# breakout_BGM111.net
KiCad netlist of a schematic drawn in EAGLE
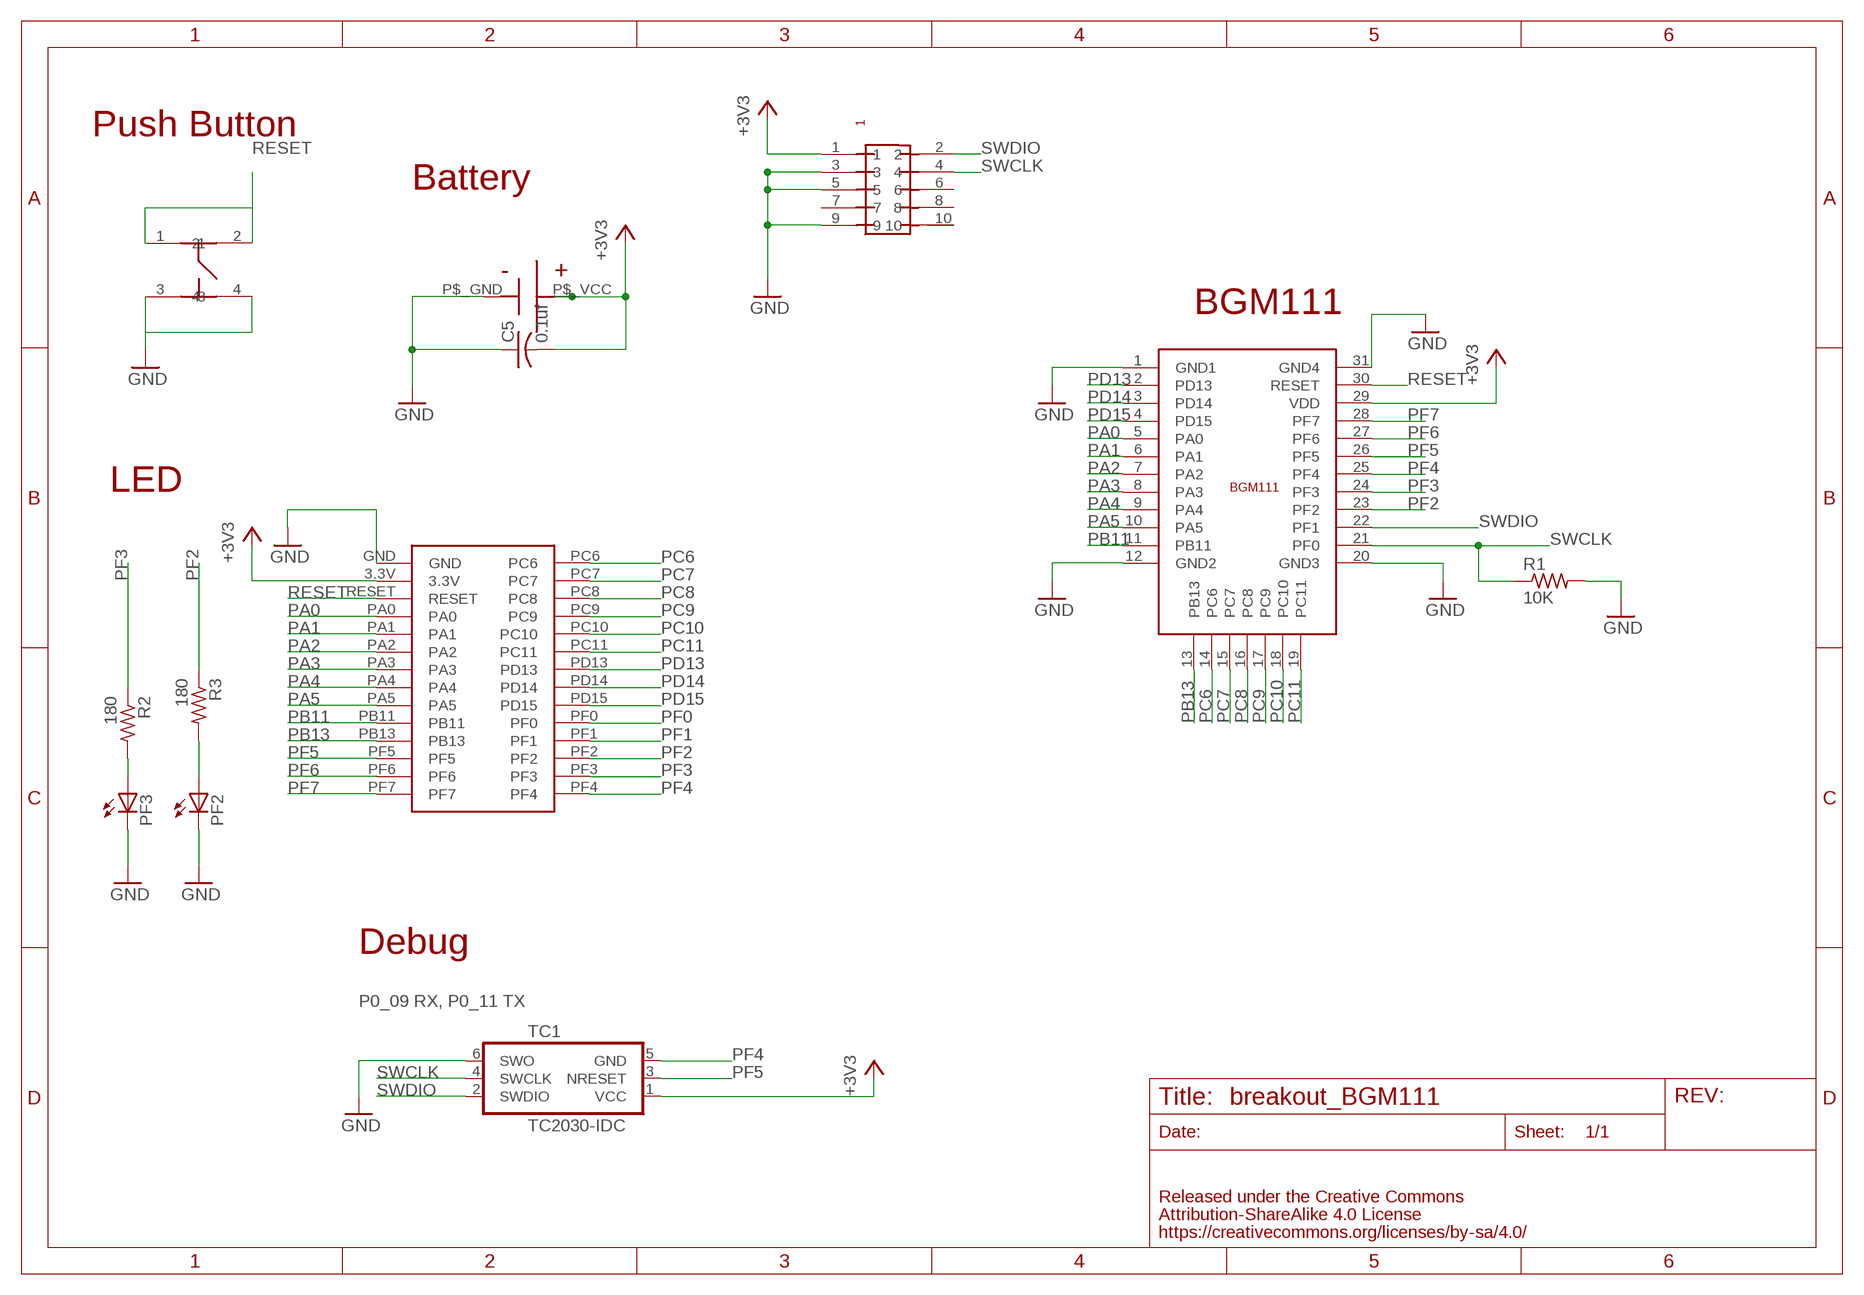
[diagram p0: schematic, sheet 1]

(export (version "E")
  (design (tool "Eeschema 10.0.6"))
  (components
    (comp (ref "C5")
      (value "0.1uf")
      (footprint "eagle-import:C0603")
      (libsource (lib "eagle-import") (part "C-USC0603"))
    )
    (comp (ref "PF2")
      (value "LEDCHIP-LED0603")
      (footprint "eagle-import:CHIP-LED0603")
      (libsource (lib "eagle-import") (part "LEDCHIP-LED0603"))
    )
    (comp (ref "PF3")
      (value "LEDCHIP-LED0603")
      (footprint "eagle-import:CHIP-LED0603")
      (libsource (lib "eagle-import") (part "LEDCHIP-LED0603"))
    )
    (comp (ref "R1")
      (value "10K")
      (footprint "eagle-import:R0603")
      (libsource (lib "eagle-import") (part "R-US_R0603"))
    )
    (comp (ref "R2")
      (value "180")
      (footprint "eagle-import:R0603")
      (libsource (lib "eagle-import") (part "R-US_R0603"))
    )
    (comp (ref "R3")
      (value "180")
      (footprint "eagle-import:R0603")
      (libsource (lib "eagle-import") (part "R-US_R0603"))
    )
    (comp (ref "TC1")
      (value "TC2030-IDC")
      (footprint "eagle-import:TC2030-IDC")
      (libsource (lib "eagle-import") (part "TC2030-IDC"))
    )
    (comp (ref "U$1")
      (value "SILICONLABS-BGM111")
      (footprint "eagle-import:SILICONLABS-BGM111")
      (libsource (lib "eagle-import") (part "SILICONLABS-BGM111"))
    )
    (comp (ref "U$2")
      (value "SMTU2450-TOP")
      (footprint "eagle-import:SMTU2450")
      (libsource (lib "eagle-import") (part "SMTU2450-TOP"))
    )
    (comp (ref "U$3")
      (value "BLE-BREAKOUT-NORDIC")
      (footprint "eagle-import:BLE-BREAKOUT-SILICONLABS")
      (libsource (lib "eagle-import") (part "BLE-BREAKOUT-NORDIC"))
    )
    (comp (ref "U$4")
      (value "PIN-HEADER-SMT(1.27MM)2X5")
      (footprint "eagle-import:PIN-HEADER-SMT(1.27MM)2X5")
      (libsource (lib "eagle-import") (part "PIN-HEADER-SMT(1.27MM)2X5"))
    )
    (comp (ref "U$5")
      (value "SWICTH-4P(KMR2)")
      (footprint "eagle-import:SWITCH-4P(KMR2)")
      (libsource (lib "eagle-import") (part "SWICTH-4P(KMR2)"))
    )
  )
  (nets
    (net (code "1") (name "+3V3") (class "Default")
      (node (ref "C5") (pin "2") (pinfunction "2_2") (pintype "passive"))
      (node (ref "TC1") (pin "1") (pinfunction "VCC_1") (pintype "passive"))
      (node (ref "U$1") (pin "29") (pinfunction "VDD_29") (pintype "bidirectional"))
      (node (ref "U$2") (pin "P$_VCC") (pinfunction "+_P$_VCC") (pintype "bidirectional"))
      (node (ref "U$3") (pin "3.3V") (pinfunction "3.3V_3.3V") (pintype "bidirectional"))
      (node (ref "U$4") (pin "1") (pinfunction "1_1") (pintype "bidirectional"))
    )
    (net (code "2") (name "/PA0") (class "Default")
      (node (ref "U$1") (pin "5") (pinfunction "PA0_5") (pintype "bidirectional"))
      (node (ref "U$3") (pin "PA0") (pinfunction "PA0_PA0") (pintype "bidirectional"))
    )
    (net (code "3") (name "/PA1") (class "Default")
      (node (ref "U$1") (pin "6") (pinfunction "PA1_6") (pintype "bidirectional"))
      (node (ref "U$3") (pin "PA1") (pinfunction "PA1_PA1") (pintype "bidirectional"))
    )
    (net (code "4") (name "/PA2") (class "Default")
      (node (ref "U$1") (pin "7") (pinfunction "PA2_7") (pintype "bidirectional"))
      (node (ref "U$3") (pin "PA2") (pinfunction "PA2_PA2") (pintype "bidirectional"))
    )
    (net (code "5") (name "/PA3") (class "Default")
      (node (ref "U$1") (pin "8") (pinfunction "PA3_8") (pintype "bidirectional"))
      (node (ref "U$3") (pin "PA3") (pinfunction "PA3_PA3") (pintype "bidirectional"))
    )
    (net (code "6") (name "/PA4") (class "Default")
      (node (ref "U$1") (pin "9") (pinfunction "PA4_9") (pintype "bidirectional"))
      (node (ref "U$3") (pin "PA4") (pinfunction "PA4_PA4") (pintype "bidirectional"))
    )
    (net (code "7") (name "/PA5") (class "Default")
      (node (ref "U$1") (pin "10") (pinfunction "PA5_10") (pintype "bidirectional"))
      (node (ref "U$3") (pin "PA5") (pinfunction "PA5_PA5") (pintype "bidirectional"))
    )
    (net (code "8") (name "/PB11") (class "Default")
      (node (ref "U$1") (pin "11") (pinfunction "PB11_11") (pintype "bidirectional"))
      (node (ref "U$3") (pin "PB11") (pinfunction "PB11_PB11") (pintype "bidirectional"))
    )
    (net (code "9") (name "/PB13") (class "Default")
      (node (ref "U$1") (pin "13") (pinfunction "PB13_13") (pintype "bidirectional"))
      (node (ref "U$3") (pin "PB13") (pinfunction "PB13_PB13") (pintype "bidirectional"))
    )
    (net (code "10") (name "/PC6") (class "Default")
      (node (ref "U$1") (pin "14") (pinfunction "PC6_14") (pintype "bidirectional"))
      (node (ref "U$3") (pin "PC6") (pinfunction "PC6_PC6") (pintype "bidirectional"))
    )
    (net (code "11") (name "/PC7") (class "Default")
      (node (ref "U$1") (pin "15") (pinfunction "PC7_15") (pintype "bidirectional"))
      (node (ref "U$3") (pin "PC7") (pinfunction "PC7_PC7") (pintype "bidirectional"))
    )
    (net (code "12") (name "/PC8") (class "Default")
      (node (ref "U$1") (pin "16") (pinfunction "PC8_16") (pintype "bidirectional"))
      (node (ref "U$3") (pin "PC8") (pinfunction "PC8_PC8") (pintype "bidirectional"))
    )
    (net (code "13") (name "/PC9") (class "Default")
      (node (ref "U$1") (pin "17") (pinfunction "PC9_17") (pintype "bidirectional"))
      (node (ref "U$3") (pin "PC9") (pinfunction "PC9_PC9") (pintype "bidirectional"))
    )
    (net (code "14") (name "/PC10") (class "Default")
      (node (ref "U$1") (pin "18") (pinfunction "PC10_18") (pintype "bidirectional"))
      (node (ref "U$3") (pin "PC10") (pinfunction "PC10_PC10") (pintype "bidirectional"))
    )
    (net (code "15") (name "/PC11") (class "Default")
      (node (ref "U$1") (pin "19") (pinfunction "PC11_19") (pintype "bidirectional"))
      (node (ref "U$3") (pin "PC11") (pinfunction "PC11_PC11") (pintype "bidirectional"))
    )
    (net (code "16") (name "/PD13") (class "Default")
      (node (ref "U$1") (pin "2") (pinfunction "PD13_2") (pintype "bidirectional"))
      (node (ref "U$3") (pin "PD13") (pinfunction "PD13_PD13") (pintype "bidirectional"))
    )
    (net (code "17") (name "/PD14") (class "Default")
      (node (ref "U$1") (pin "3") (pinfunction "PD14_3") (pintype "bidirectional"))
      (node (ref "U$3") (pin "PD14") (pinfunction "PD14_PD14") (pintype "bidirectional"))
    )
    (net (code "18") (name "/PD15") (class "Default")
      (node (ref "U$1") (pin "4") (pinfunction "PD15_4") (pintype "bidirectional"))
      (node (ref "U$3") (pin "PD15") (pinfunction "PD15_PD15") (pintype "bidirectional"))
    )
    (net (code "19") (name "/PF0") (class "Default")
      (node (ref "U$3") (pin "PF0") (pinfunction "PF0_PF0") (pintype "bidirectional"))
    )
    (net (code "20") (name "/PF1") (class "Default")
      (node (ref "U$3") (pin "PF1") (pinfunction "PF1_PF1") (pintype "bidirectional"))
    )
    (net (code "21") (name "/PF2") (class "Default")
      (node (ref "R3") (pin "1") (pinfunction "1_1") (pintype "passive"))
      (node (ref "U$1") (pin "23") (pinfunction "PF2_23") (pintype "bidirectional"))
      (node (ref "U$3") (pin "PF2") (pinfunction "PF2_PF2") (pintype "bidirectional"))
    )
    (net (code "22") (name "/PF3") (class "Default")
      (node (ref "R2") (pin "1") (pinfunction "1_1") (pintype "passive"))
      (node (ref "U$1") (pin "24") (pinfunction "PF3_24") (pintype "bidirectional"))
      (node (ref "U$3") (pin "PF3") (pinfunction "PF3_PF3") (pintype "bidirectional"))
    )
    (net (code "23") (name "/PF4") (class "Default")
      (node (ref "TC1") (pin "5") (pinfunction "GND_5") (pintype "passive"))
      (node (ref "U$1") (pin "25") (pinfunction "PF4_25") (pintype "bidirectional"))
      (node (ref "U$3") (pin "PF4") (pinfunction "PF4_PF4") (pintype "bidirectional"))
    )
    (net (code "24") (name "/PF5") (class "Default")
      (node (ref "TC1") (pin "3") (pinfunction "NRESET_3") (pintype "passive"))
      (node (ref "U$1") (pin "26") (pinfunction "PF5_26") (pintype "bidirectional"))
      (node (ref "U$3") (pin "PF5") (pinfunction "PF5_PF5") (pintype "bidirectional"))
    )
    (net (code "25") (name "/PF6") (class "Default")
      (node (ref "U$1") (pin "27") (pinfunction "PF6_27") (pintype "bidirectional"))
      (node (ref "U$3") (pin "PF6") (pinfunction "PF6_PF6") (pintype "bidirectional"))
    )
    (net (code "26") (name "/PF7") (class "Default")
      (node (ref "U$1") (pin "28") (pinfunction "PF7_28") (pintype "bidirectional"))
      (node (ref "U$3") (pin "PF7") (pinfunction "PF7_PF7") (pintype "bidirectional"))
    )
    (net (code "27") (name "/RESET") (class "Default")
      (node (ref "U$1") (pin "30") (pinfunction "RESET_30") (pintype "bidirectional"))
      (node (ref "U$3") (pin "RESET") (pinfunction "RESET_RESET") (pintype "bidirectional"))
      (node (ref "U$5") (pin "1") (pinfunction "1_1") (pintype "bidirectional"))
      (node (ref "U$5") (pin "2") (pinfunction "2_2") (pintype "bidirectional"))
    )
    (net (code "28") (name "/SWCLK") (class "Default")
      (node (ref "R1") (pin "1") (pinfunction "1_1") (pintype "passive"))
      (node (ref "TC1") (pin "4") (pinfunction "SWCLK_4") (pintype "passive"))
      (node (ref "U$1") (pin "21") (pinfunction "PF0_21") (pintype "bidirectional"))
      (node (ref "U$4") (pin "4") (pinfunction "4_4") (pintype "bidirectional"))
    )
    (net (code "29") (name "/SWDIO") (class "Default")
      (node (ref "TC1") (pin "2") (pinfunction "SWDIO_2") (pintype "passive"))
      (node (ref "U$1") (pin "22") (pinfunction "PF1_22") (pintype "bidirectional"))
      (node (ref "U$4") (pin "2") (pinfunction "2_2") (pintype "bidirectional"))
    )
    (net (code "30") (name "GND") (class "Default")
      (node (ref "C5") (pin "1") (pinfunction "1_1") (pintype "passive"))
      (node (ref "PF2") (pin "C") (pinfunction "C_C") (pintype "passive"))
      (node (ref "PF3") (pin "C") (pinfunction "C_C") (pintype "passive"))
      (node (ref "R1") (pin "2") (pinfunction "2_2") (pintype "passive"))
      (node (ref "TC1") (pin "6") (pinfunction "SWO_6") (pintype "passive"))
      (node (ref "U$1") (pin "1") (pinfunction "GND1_1") (pintype "bidirectional"))
      (node (ref "U$1") (pin "12") (pinfunction "GND2_12") (pintype "bidirectional"))
      (node (ref "U$1") (pin "20") (pinfunction "GND3_20") (pintype "bidirectional"))
      (node (ref "U$1") (pin "31") (pinfunction "GND4_31") (pintype "bidirectional"))
      (node (ref "U$2") (pin "P$_GND") (pinfunction "-_P$_GND") (pintype "bidirectional"))
      (node (ref "U$3") (pin "GND") (pinfunction "GND_GND") (pintype "bidirectional"))
      (node (ref "U$4") (pin "3") (pinfunction "3_3") (pintype "bidirectional"))
      (node (ref "U$4") (pin "5") (pinfunction "5_5") (pintype "bidirectional"))
      (node (ref "U$4") (pin "9") (pinfunction "9_9") (pintype "bidirectional"))
      (node (ref "U$5") (pin "3") (pinfunction "3_3") (pintype "bidirectional"))
      (node (ref "U$5") (pin "4") (pinfunction "4_4") (pintype "bidirectional"))
    )
    (net (code "31") (name "Net-(PF2-PadA)") (class "Default")
      (node (ref "PF2") (pin "A") (pinfunction "A_A") (pintype "passive"))
      (node (ref "R3") (pin "2") (pinfunction "2_2") (pintype "passive"))
    )
    (net (code "32") (name "Net-(PF3-PadA)") (class "Default")
      (node (ref "PF3") (pin "A") (pinfunction "A_A") (pintype "passive"))
      (node (ref "R2") (pin "2") (pinfunction "2_2") (pintype "passive"))
    )
    (net (code "33") (name "unconnected-(U$4-Pad6)") (class "Default")
      (node (ref "U$4") (pin "6") (pinfunction "6_6") (pintype "bidirectional"))
    )
    (net (code "34") (name "unconnected-(U$4-Pad7)") (class "Default")
      (node (ref "U$4") (pin "7") (pinfunction "7_7") (pintype "bidirectional"))
    )
    (net (code "35") (name "unconnected-(U$4-Pad8)") (class "Default")
      (node (ref "U$4") (pin "8") (pinfunction "8_8") (pintype "bidirectional"))
    )
    (net (code "36") (name "unconnected-(U$4-Pad10)") (class "Default")
      (node (ref "U$4") (pin "10") (pinfunction "10_10") (pintype "bidirectional"))
    )
  )
)
